# matrix_scanner.net
KiCad netlist of a schematic drawn in EAGLE
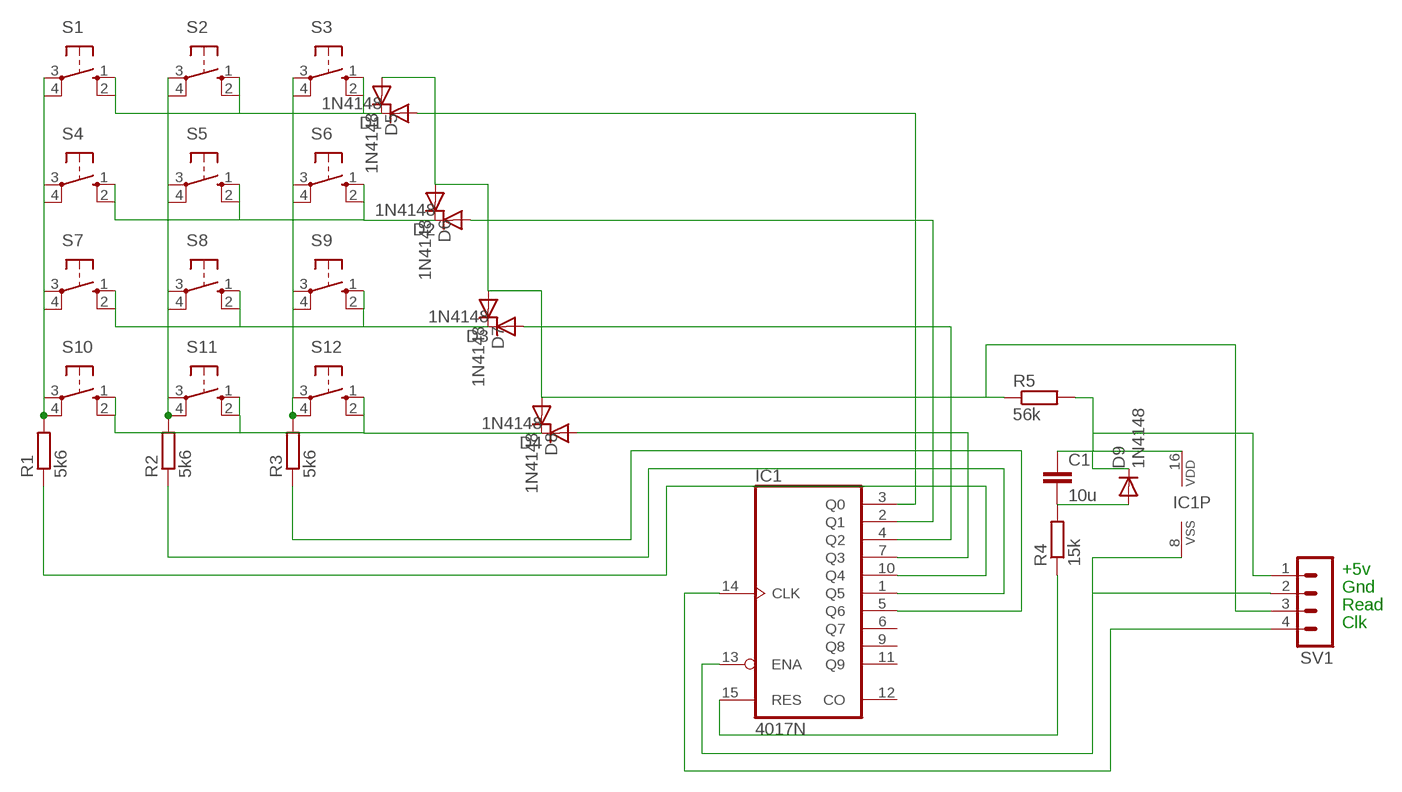
[diagram p0: schematic, sheet 1]

(export (version "E")
  (design (tool "Eeschema 10.0.6"))
  (components
    (comp (ref "C1")
      (value "10u")
      (footprint "eagle-import:C025-050X050")
      (libsource (lib "eagle-import") (part "C-EU025-050X050"))
    )
    (comp (ref "D1")
      (value "1N4148")
      (footprint "eagle-import:DO35-7")
      (libsource (lib "eagle-import") (part "1N4148DO35-7"))
    )
    (comp (ref "D2")
      (value "1N4148")
      (footprint "eagle-import:DO35-7")
      (libsource (lib "eagle-import") (part "1N4148DO35-7"))
    )
    (comp (ref "D3")
      (value "1N4148")
      (footprint "eagle-import:DO35-7")
      (libsource (lib "eagle-import") (part "1N4148DO35-7"))
    )
    (comp (ref "D4")
      (value "1N4148")
      (footprint "eagle-import:DO35-7")
      (libsource (lib "eagle-import") (part "1N4148DO35-7"))
    )
    (comp (ref "D5")
      (value "1N4148")
      (footprint "eagle-import:DO35-7")
      (libsource (lib "eagle-import") (part "1N4148DO35-7"))
    )
    (comp (ref "D6")
      (value "1N4148")
      (footprint "eagle-import:DO35-7")
      (libsource (lib "eagle-import") (part "1N4148DO35-7"))
    )
    (comp (ref "D7")
      (value "1N4148")
      (footprint "eagle-import:DO35-7")
      (libsource (lib "eagle-import") (part "1N4148DO35-7"))
    )
    (comp (ref "D8")
      (value "1N4148")
      (footprint "eagle-import:DO35-7")
      (libsource (lib "eagle-import") (part "1N4148DO35-7"))
    )
    (comp (ref "D9")
      (value "1N4148")
      (footprint "eagle-import:DO35-7")
      (libsource (lib "eagle-import") (part "1N4148DO35-7"))
    )
    (comp (ref "IC1")
      (value "4017N")
      (footprint "eagle-import:DIL16")
      (libsource (lib "eagle-import") (part "4017N"))
    )
    (comp (ref "R1")
      (value "5k6")
      (footprint "eagle-import:0204_7")
      (libsource (lib "eagle-import") (part "R-EU_0204/7"))
    )
    (comp (ref "R2")
      (value "5k6")
      (footprint "eagle-import:0204_7")
      (libsource (lib "eagle-import") (part "R-EU_0204/7"))
    )
    (comp (ref "R3")
      (value "5k6")
      (footprint "eagle-import:0204_7")
      (libsource (lib "eagle-import") (part "R-EU_0204/7"))
    )
    (comp (ref "R4")
      (value "15k")
      (footprint "eagle-import:0204_7")
      (libsource (lib "eagle-import") (part "R-EU_0204/7"))
    )
    (comp (ref "R5")
      (value "56k")
      (footprint "eagle-import:0204_7")
      (libsource (lib "eagle-import") (part "R-EU_0204/7"))
    )
    (comp (ref "S1")
      (value "10-XX")
      (footprint "eagle-import:B3F-10XX")
      (fields (field (name "MPN") "B3F-1000"))
      (libsource (lib "eagle-import") (part "10-XX"))
    )
    (comp (ref "S2")
      (value "10-XX")
      (footprint "eagle-import:B3F-10XX")
      (fields (field (name "MPN") "B3F-1000"))
      (libsource (lib "eagle-import") (part "10-XX"))
    )
    (comp (ref "S3")
      (value "10-XX")
      (footprint "eagle-import:B3F-10XX")
      (fields (field (name "MPN") "B3F-1000"))
      (libsource (lib "eagle-import") (part "10-XX"))
    )
    (comp (ref "S4")
      (value "10-XX")
      (footprint "eagle-import:B3F-10XX")
      (fields (field (name "MPN") "B3F-1000"))
      (libsource (lib "eagle-import") (part "10-XX"))
    )
    (comp (ref "S5")
      (value "10-XX")
      (footprint "eagle-import:B3F-10XX")
      (fields (field (name "MPN") "B3F-1000"))
      (libsource (lib "eagle-import") (part "10-XX"))
    )
    (comp (ref "S6")
      (value "10-XX")
      (footprint "eagle-import:B3F-10XX")
      (fields (field (name "MPN") "B3F-1000"))
      (libsource (lib "eagle-import") (part "10-XX"))
    )
    (comp (ref "S7")
      (value "10-XX")
      (footprint "eagle-import:B3F-10XX")
      (fields (field (name "MPN") "B3F-1000"))
      (libsource (lib "eagle-import") (part "10-XX"))
    )
    (comp (ref "S8")
      (value "10-XX")
      (footprint "eagle-import:B3F-10XX")
      (fields (field (name "MPN") "B3F-1000"))
      (libsource (lib "eagle-import") (part "10-XX"))
    )
    (comp (ref "S9")
      (value "10-XX")
      (footprint "eagle-import:B3F-10XX")
      (fields (field (name "MPN") "B3F-1000"))
      (libsource (lib "eagle-import") (part "10-XX"))
    )
    (comp (ref "S10")
      (value "10-XX")
      (footprint "eagle-import:B3F-10XX")
      (fields (field (name "MPN") "B3F-1000"))
      (libsource (lib "eagle-import") (part "10-XX"))
    )
    (comp (ref "S11")
      (value "10-XX")
      (footprint "eagle-import:B3F-10XX")
      (fields (field (name "MPN") "B3F-1000"))
      (libsource (lib "eagle-import") (part "10-XX"))
    )
    (comp (ref "S12")
      (value "10-XX")
      (footprint "eagle-import:B3F-10XX")
      (fields (field (name "MPN") "B3F-1000"))
      (libsource (lib "eagle-import") (part "10-XX"))
    )
    (comp (ref "SV1")
      (value "MA04-1")
      (footprint "eagle-import:MA04-1")
      (libsource (lib "eagle-import") (part "MA04-1"))
    )
  )
  (nets
    (net (code "1") (name "Net-(C1-Pad2)") (class "Default")
      (node (ref "C1") (pin "2") (pinfunction "2_2") (pintype "passive"))
      (node (ref "D9") (pin "A") (pinfunction "A_A") (pintype "passive"))
      (node (ref "R4") (pin "2") (pinfunction "2_2") (pintype "passive"))
    )
    (net (code "2") (name "Net-(D5-PadA)") (class "Default")
      (node (ref "D5") (pin "A") (pinfunction "A_A") (pintype "passive"))
      (node (ref "D6") (pin "A") (pinfunction "A_A") (pintype "passive"))
      (node (ref "D7") (pin "A") (pinfunction "A_A") (pintype "passive"))
      (node (ref "D8") (pin "A") (pinfunction "A_A") (pintype "passive"))
      (node (ref "R5") (pin "1") (pinfunction "1_1") (pintype "passive"))
      (node (ref "SV1") (pin "3") (pinfunction "3_3") (pintype "passive"))
    )
    (net (code "3") (name "Net-(IC1A-CLK)") (class "Default")
      (node (ref "IC1") (pin "14") (pinfunction "CLK_14") (pintype "input"))
      (node (ref "SV1") (pin "4") (pinfunction "4_4") (pintype "passive"))
    )
    (net (code "4") (name "Net-(IC1A-ENA)") (class "Default")
      (node (ref "IC1") (pin "13") (pinfunction "ENA_13") (pintype "input"))
      (node (ref "IC1") (pin "8") (pinfunction "VSS_8") (pintype "power_in"))
      (node (ref "SV1") (pin "2") (pinfunction "2_2") (pintype "passive"))
    )
    (net (code "5") (name "Net-(IC1A-Q0)") (class "Default")
      (node (ref "D1") (pin "A") (pinfunction "A_A") (pintype "passive"))
      (node (ref "IC1") (pin "3") (pinfunction "Q0_3") (pintype "output"))
    )
    (net (code "6") (name "Net-(IC1A-Q1)") (class "Default")
      (node (ref "D2") (pin "A") (pinfunction "A_A") (pintype "passive"))
      (node (ref "IC1") (pin "2") (pinfunction "Q1_2") (pintype "output"))
    )
    (net (code "7") (name "Net-(IC1A-Q2)") (class "Default")
      (node (ref "D3") (pin "A") (pinfunction "A_A") (pintype "passive"))
      (node (ref "IC1") (pin "4") (pinfunction "Q2_4") (pintype "output"))
    )
    (net (code "8") (name "Net-(IC1A-Q3)") (class "Default")
      (node (ref "D4") (pin "A") (pinfunction "A_A") (pintype "passive"))
      (node (ref "IC1") (pin "7") (pinfunction "Q3_7") (pintype "output"))
    )
    (net (code "9") (name "Net-(IC1A-Q4)") (class "Default")
      (node (ref "IC1") (pin "10") (pinfunction "Q4_10") (pintype "output"))
      (node (ref "R1") (pin "1") (pinfunction "1_1") (pintype "passive"))
    )
    (net (code "10") (name "Net-(IC1A-Q5)") (class "Default")
      (node (ref "IC1") (pin "1") (pinfunction "Q5_1") (pintype "output"))
      (node (ref "R2") (pin "1") (pinfunction "1_1") (pintype "passive"))
    )
    (net (code "11") (name "Net-(IC1A-Q6)") (class "Default")
      (node (ref "IC1") (pin "5") (pinfunction "Q6_5") (pintype "output"))
      (node (ref "R3") (pin "1") (pinfunction "1_1") (pintype "passive"))
    )
    (net (code "12") (name "Net-(IC1A-RES)") (class "Default")
      (node (ref "IC1") (pin "15") (pinfunction "RES_15") (pintype "input"))
      (node (ref "R4") (pin "1") (pinfunction "1_1") (pintype "passive"))
    )
    (net (code "13") (name "Net-(IC1B-VDD)") (class "Default")
      (node (ref "C1") (pin "1") (pinfunction "1_1") (pintype "passive"))
      (node (ref "D9") (pin "C") (pinfunction "C_C") (pintype "passive"))
      (node (ref "IC1") (pin "16") (pinfunction "VDD_16") (pintype "power_in"))
      (node (ref "R5") (pin "2") (pinfunction "2_2") (pintype "passive"))
      (node (ref "SV1") (pin "1") (pinfunction "1_1") (pintype "passive"))
    )
    (net (code "14") (name "Net-(S1-P)") (class "Default")
      (node (ref "R1") (pin "2") (pinfunction "2_2") (pintype "passive"))
      (node (ref "S1") (pin "3") (pinfunction "P_3") (pintype "passive"))
      (node (ref "S1") (pin "4") (pinfunction "P1_4") (pintype "passive"))
      (node (ref "S10") (pin "3") (pinfunction "P_3") (pintype "passive"))
      (node (ref "S10") (pin "4") (pinfunction "P1_4") (pintype "passive"))
      (node (ref "S4") (pin "3") (pinfunction "P_3") (pintype "passive"))
      (node (ref "S4") (pin "4") (pinfunction "P1_4") (pintype "passive"))
      (node (ref "S7") (pin "3") (pinfunction "P_3") (pintype "passive"))
      (node (ref "S7") (pin "4") (pinfunction "P1_4") (pintype "passive"))
    )
    (net (code "15") (name "Net-(S1-S)") (class "Default")
      (node (ref "D1") (pin "C") (pinfunction "C_C") (pintype "passive"))
      (node (ref "D5") (pin "C") (pinfunction "C_C") (pintype "passive"))
      (node (ref "S1") (pin "1") (pinfunction "S_1") (pintype "passive"))
      (node (ref "S1") (pin "2") (pinfunction "S1_2") (pintype "passive"))
      (node (ref "S2") (pin "1") (pinfunction "S_1") (pintype "passive"))
      (node (ref "S2") (pin "2") (pinfunction "S1_2") (pintype "passive"))
      (node (ref "S3") (pin "1") (pinfunction "S_1") (pintype "passive"))
      (node (ref "S3") (pin "2") (pinfunction "S1_2") (pintype "passive"))
    )
    (net (code "16") (name "Net-(S4-S)") (class "Default")
      (node (ref "D2") (pin "C") (pinfunction "C_C") (pintype "passive"))
      (node (ref "D6") (pin "C") (pinfunction "C_C") (pintype "passive"))
      (node (ref "S4") (pin "1") (pinfunction "S_1") (pintype "passive"))
      (node (ref "S4") (pin "2") (pinfunction "S1_2") (pintype "passive"))
      (node (ref "S5") (pin "1") (pinfunction "S_1") (pintype "passive"))
      (node (ref "S5") (pin "2") (pinfunction "S1_2") (pintype "passive"))
      (node (ref "S6") (pin "1") (pinfunction "S_1") (pintype "passive"))
      (node (ref "S6") (pin "2") (pinfunction "S1_2") (pintype "passive"))
    )
    (net (code "17") (name "Net-(S7-S)") (class "Default")
      (node (ref "D3") (pin "C") (pinfunction "C_C") (pintype "passive"))
      (node (ref "D7") (pin "C") (pinfunction "C_C") (pintype "passive"))
      (node (ref "S7") (pin "1") (pinfunction "S_1") (pintype "passive"))
      (node (ref "S7") (pin "2") (pinfunction "S1_2") (pintype "passive"))
      (node (ref "S8") (pin "1") (pinfunction "S_1") (pintype "passive"))
      (node (ref "S8") (pin "2") (pinfunction "S1_2") (pintype "passive"))
      (node (ref "S9") (pin "1") (pinfunction "S_1") (pintype "passive"))
      (node (ref "S9") (pin "2") (pinfunction "S1_2") (pintype "passive"))
    )
    (net (code "18") (name "Net-(S10-S)") (class "Default")
      (node (ref "D4") (pin "C") (pinfunction "C_C") (pintype "passive"))
      (node (ref "D8") (pin "C") (pinfunction "C_C") (pintype "passive"))
      (node (ref "S10") (pin "1") (pinfunction "S_1") (pintype "passive"))
      (node (ref "S10") (pin "2") (pinfunction "S1_2") (pintype "passive"))
      (node (ref "S11") (pin "1") (pinfunction "S_1") (pintype "passive"))
      (node (ref "S11") (pin "2") (pinfunction "S1_2") (pintype "passive"))
      (node (ref "S12") (pin "1") (pinfunction "S_1") (pintype "passive"))
      (node (ref "S12") (pin "2") (pinfunction "S1_2") (pintype "passive"))
    )
    (net (code "19") (name "Net-(S11-P)") (class "Default")
      (node (ref "R2") (pin "2") (pinfunction "2_2") (pintype "passive"))
      (node (ref "S11") (pin "3") (pinfunction "P_3") (pintype "passive"))
      (node (ref "S11") (pin "4") (pinfunction "P1_4") (pintype "passive"))
      (node (ref "S2") (pin "3") (pinfunction "P_3") (pintype "passive"))
      (node (ref "S2") (pin "4") (pinfunction "P1_4") (pintype "passive"))
      (node (ref "S5") (pin "3") (pinfunction "P_3") (pintype "passive"))
      (node (ref "S5") (pin "4") (pinfunction "P1_4") (pintype "passive"))
      (node (ref "S8") (pin "3") (pinfunction "P_3") (pintype "passive"))
      (node (ref "S8") (pin "4") (pinfunction "P1_4") (pintype "passive"))
    )
    (net (code "20") (name "Net-(S12-P)") (class "Default")
      (node (ref "R3") (pin "2") (pinfunction "2_2") (pintype "passive"))
      (node (ref "S12") (pin "3") (pinfunction "P_3") (pintype "passive"))
      (node (ref "S12") (pin "4") (pinfunction "P1_4") (pintype "passive"))
      (node (ref "S3") (pin "3") (pinfunction "P_3") (pintype "passive"))
      (node (ref "S3") (pin "4") (pinfunction "P1_4") (pintype "passive"))
      (node (ref "S6") (pin "3") (pinfunction "P_3") (pintype "passive"))
      (node (ref "S6") (pin "4") (pinfunction "P1_4") (pintype "passive"))
      (node (ref "S9") (pin "3") (pinfunction "P_3") (pintype "passive"))
      (node (ref "S9") (pin "4") (pinfunction "P1_4") (pintype "passive"))
    )
    (net (code "21") (name "unconnected-(IC1A-CO-Pad12)") (class "Default")
      (node (ref "IC1") (pin "12") (pinfunction "CO_12") (pintype "output"))
    )
    (net (code "22") (name "unconnected-(IC1A-Q7-Pad6)") (class "Default")
      (node (ref "IC1") (pin "6") (pinfunction "Q7_6") (pintype "output"))
    )
    (net (code "23") (name "unconnected-(IC1A-Q8-Pad9)") (class "Default")
      (node (ref "IC1") (pin "9") (pinfunction "Q8_9") (pintype "output"))
    )
    (net (code "24") (name "unconnected-(IC1A-Q9-Pad11)") (class "Default")
      (node (ref "IC1") (pin "11") (pinfunction "Q9_11") (pintype "output"))
    )
  )
)
